# Sheet3.net
KiCad netlist of a schematic drawn in Altium Designer
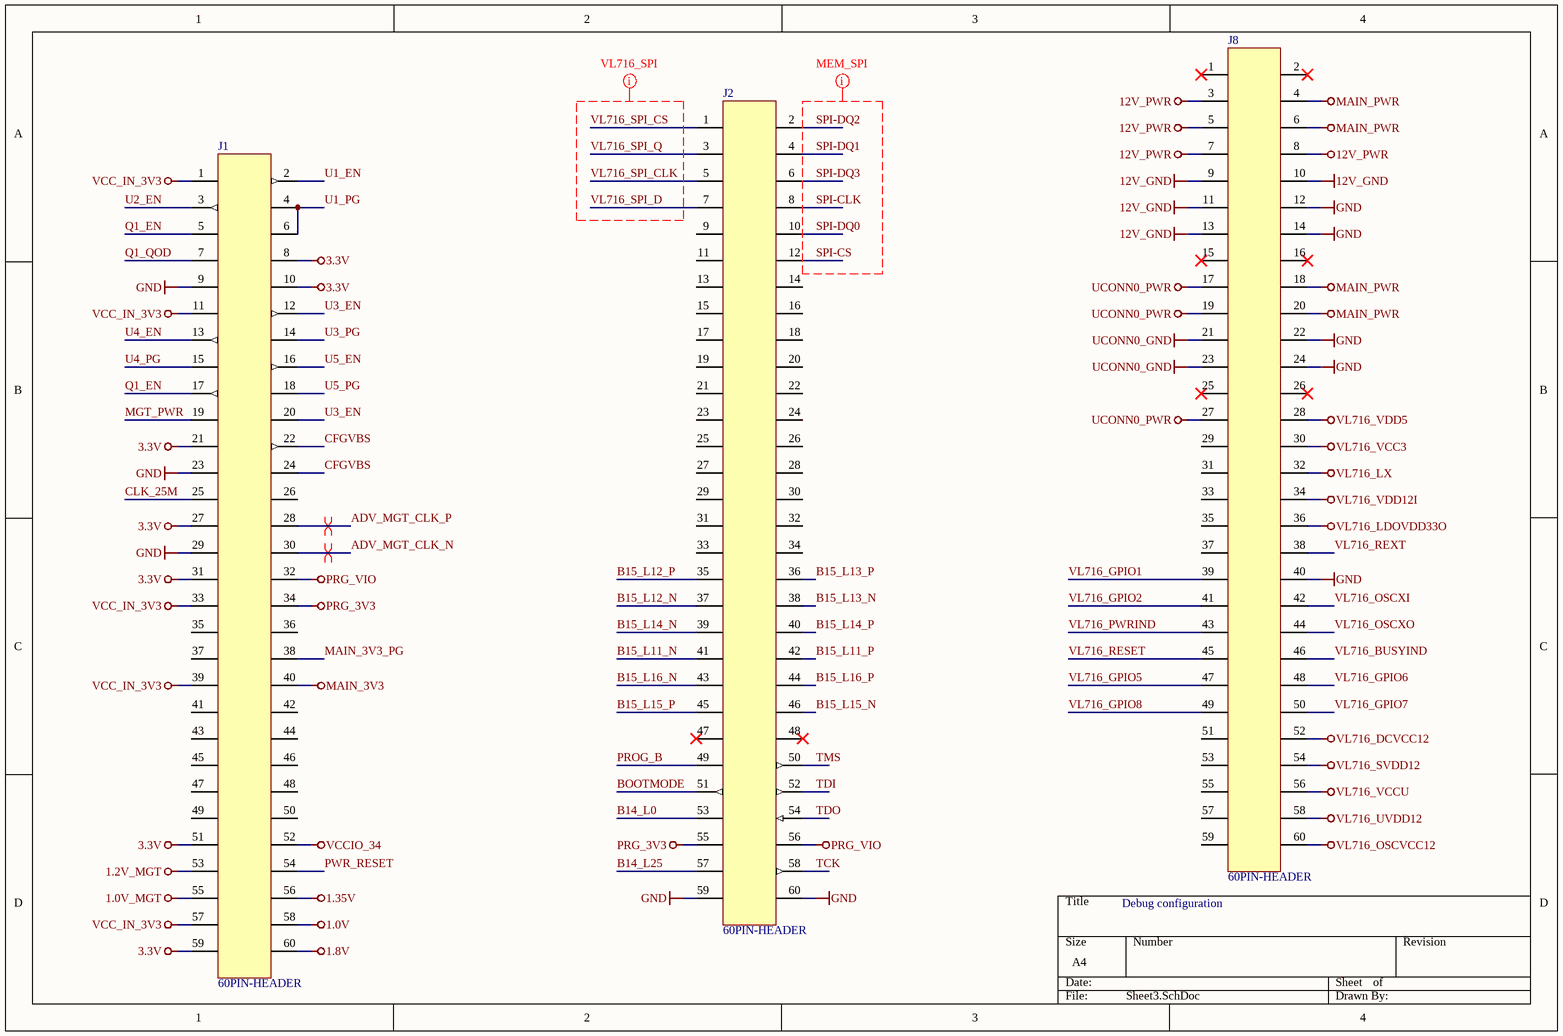
[diagram p0: Sheet3.SchDoc]

(export (version "E")
  (design (tool "Eeschema 10.0.6"))
  (components
    (comp (ref "J1")
      (value "60PIN-HEADER")
      (footprint "60PIN-HEADER")
      (description "2.54mm 60-pin header")
      (libsource (lib "Integrated_Library") (part "60PIN-HEADER"))
    )
    (comp (ref "J2")
      (value "60PIN-HEADER")
      (footprint "60PIN-HEADER")
      (description "2.54mm 60-pin header")
      (libsource (lib "Integrated_Library") (part "60PIN-HEADER"))
    )
    (comp (ref "J8")
      (value "60PIN-HEADER")
      (footprint "60PIN-HEADER")
      (description "2.54mm 60-pin header")
      (libsource (lib "Integrated_Library") (part "60PIN-HEADER"))
    )
  )
  (nets
    (net (code "1") (name "/ADV_MGT_CLK_N") (class "Default")
      (node (ref "J1") (pin "30") (pintype "passive"))
    )
    (net (code "2") (name "/ADV_MGT_CLK_P") (class "Default")
      (node (ref "J1") (pin "28") (pintype "passive"))
    )
    (net (code "3") (name "/B14_L0") (class "Default") (node (ref "J2") (pin "53") (pintype "passive")))
    (net (code "4") (name "/B14_L25") (class "Default") (node (ref "J2") (pin "57") (pintype "passive")))
    (net (code "5") (name "/B15_L11_N") (class "Default") (node (ref "J2") (pin "41") (pintype "passive")))
    (net (code "6") (name "/B15_L11_P") (class "Default") (node (ref "J2") (pin "42") (pintype "passive")))
    (net (code "7") (name "/B15_L12_N") (class "Default") (node (ref "J2") (pin "37") (pintype "passive")))
    (net (code "8") (name "/B15_L12_P") (class "Default") (node (ref "J2") (pin "35") (pintype "passive")))
    (net (code "9") (name "/B15_L13_N") (class "Default") (node (ref "J2") (pin "38") (pintype "passive")))
    (net (code "10") (name "/B15_L13_P") (class "Default") (node (ref "J2") (pin "36") (pintype "passive")))
    (net (code "11") (name "/B15_L14_N") (class "Default") (node (ref "J2") (pin "39") (pintype "passive")))
    (net (code "12") (name "/B15_L14_P") (class "Default") (node (ref "J2") (pin "40") (pintype "passive")))
    (net (code "13") (name "/B15_L15_N") (class "Default") (node (ref "J2") (pin "46") (pintype "passive")))
    (net (code "14") (name "/B15_L15_P") (class "Default") (node (ref "J2") (pin "45") (pintype "passive")))
    (net (code "15") (name "/B15_L16_N") (class "Default") (node (ref "J2") (pin "43") (pintype "passive")))
    (net (code "16") (name "/B15_L16_P") (class "Default") (node (ref "J2") (pin "44") (pintype "passive")))
    (net (code "17") (name "/BOOTMODE") (class "Default") (node (ref "J2") (pin "51") (pintype "passive")))
    (net (code "18") (name "/CFGVBS") (class "Default")
      (node (ref "J1") (pin "22") (pintype "output"))
      (node (ref "J1") (pin "24") (pintype "passive"))
    )
    (net (code "19") (name "/CLK_25M") (class "Default") (node (ref "J1") (pin "25") (pintype "passive")))
    (net (code "20") (name "/MAIN_3V3_PG") (class "Default") (node (ref "J1") (pin "38") (pintype "passive")))
    (net (code "21") (name "/MGT_PWR") (class "Default") (node (ref "J1") (pin "19") (pintype "passive")))
    (net (code "22") (name "/PROG_B") (class "Default") (node (ref "J2") (pin "49") (pintype "passive")))
    (net (code "23") (name "/PWR_RESET") (class "Default") (node (ref "J1") (pin "54") (pintype "passive")))
    (net (code "24") (name "/Q1_EN") (class "Default")
      (node (ref "J1") (pin "17") (pintype "output"))
      (node (ref "J1") (pin "5") (pintype "passive"))
    )
    (net (code "25") (name "/Q1_QOD") (class "Default") (node (ref "J1") (pin "7") (pintype "passive")))
    (net (code "26") (name "/SPI-CLK") (class "Default") (node (ref "J2") (pin "8") (pintype "power_in")))
    (net (code "27") (name "/SPI-CS") (class "Default") (node (ref "J2") (pin "12") (pintype "output")))
    (net (code "28") (name "/SPI-DQ0") (class "Default") (node (ref "J2") (pin "10") (pintype "power_in")))
    (net (code "29") (name "/SPI-DQ1") (class "Default") (node (ref "J2") (pin "4") (pintype "passive")))
    (net (code "30") (name "/SPI-DQ2") (class "Default") (node (ref "J2") (pin "2") (pintype "output")))
    (net (code "31") (name "/SPI-DQ3") (class "Default") (node (ref "J2") (pin "6") (pintype "passive")))
    (net (code "32") (name "/TCK") (class "Default") (node (ref "J2") (pin "58") (pintype "passive")))
    (net (code "33") (name "/TDI") (class "Default") (node (ref "J2") (pin "52") (pintype "passive")))
    (net (code "34") (name "/TDO") (class "Default") (node (ref "J2") (pin "54") (pintype "passive")))
    (net (code "35") (name "/TMS") (class "Default") (node (ref "J2") (pin "50") (pintype "passive")))
    (net (code "36") (name "/U1_EN") (class "Default") (node (ref "J1") (pin "2") (pintype "output")))
    (net (code "37") (name "/U1_PG") (class "Default")
      (node (ref "J1") (pin "4") (pintype "passive"))
      (node (ref "J1") (pin "6") (pintype "passive"))
    )
    (net (code "38") (name "/U2_EN") (class "Default") (node (ref "J1") (pin "3") (pintype "output")))
    (net (code "39") (name "/U3_EN") (class "Default")
      (node (ref "J1") (pin "12") (pintype "output"))
      (node (ref "J1") (pin "20") (pintype "passive"))
    )
    (net (code "40") (name "/U3_PG") (class "Default") (node (ref "J1") (pin "14") (pintype "passive")))
    (net (code "41") (name "/U4_EN") (class "Default") (node (ref "J1") (pin "13") (pintype "output")))
    (net (code "42") (name "/U4_PG") (class "Default") (node (ref "J1") (pin "15") (pintype "passive")))
    (net (code "43") (name "/U5_EN") (class "Default") (node (ref "J1") (pin "16") (pintype "output")))
    (net (code "44") (name "/U5_PG") (class "Default") (node (ref "J1") (pin "18") (pintype "passive")))
    (net (code "45") (name "/VL716_BUSYIND") (class "Default")
      (node (ref "J8") (pin "46") (pintype "passive"))
    )
    (net (code "46") (name "/VL716_GPIO1") (class "Default") (node (ref "J8") (pin "39") (pintype "passive")))
    (net (code "47") (name "/VL716_GPIO2") (class "Default") (node (ref "J8") (pin "41") (pintype "passive")))
    (net (code "48") (name "/VL716_GPIO5") (class "Default") (node (ref "J8") (pin "47") (pintype "passive")))
    (net (code "49") (name "/VL716_GPIO6") (class "Default") (node (ref "J8") (pin "48") (pintype "passive")))
    (net (code "50") (name "/VL716_GPIO7") (class "Default") (node (ref "J8") (pin "50") (pintype "passive")))
    (net (code "51") (name "/VL716_GPIO8") (class "Default") (node (ref "J8") (pin "49") (pintype "passive")))
    (net (code "52") (name "/VL716_OSCXI") (class "Default") (node (ref "J8") (pin "42") (pintype "passive")))
    (net (code "53") (name "/VL716_OSCXO") (class "Default") (node (ref "J8") (pin "44") (pintype "passive")))
    (net (code "54") (name "/VL716_PWRIND") (class "Default")
      (node (ref "J8") (pin "43") (pintype "passive"))
    )
    (net (code "55") (name "/VL716_RESET") (class "Default") (node (ref "J8") (pin "45") (pintype "passive")))
    (net (code "56") (name "/VL716_REXT") (class "Default") (node (ref "J8") (pin "38") (pintype "passive")))
    (net (code "57") (name "/VL716_SPI_CLK") (class "Default")
      (node (ref "J2") (pin "5") (pintype "passive"))
    )
    (net (code "58") (name "/VL716_SPI_CS") (class "Default") (node (ref "J2") (pin "1") (pintype "passive")))
    (net (code "59") (name "/VL716_SPI_D") (class "Default") (node (ref "J2") (pin "7") (pintype "passive")))
    (net (code "60") (name "/VL716_SPI_Q") (class "Default") (node (ref "J2") (pin "3") (pintype "output")))
    (net (code "61") (name "1.0V") (class "Default") (node (ref "J1") (pin "58") (pintype "passive")))
    (net (code "62") (name "1.0V_MGT") (class "Default") (node (ref "J1") (pin "55") (pintype "passive")))
    (net (code "63") (name "1.2V_MGT") (class "Default") (node (ref "J1") (pin "53") (pintype "passive")))
    (net (code "64") (name "1.8V") (class "Default") (node (ref "J1") (pin "60") (pintype "passive")))
    (net (code "65") (name "1.35V") (class "Default") (node (ref "J1") (pin "56") (pintype "passive")))
    (net (code "66") (name "3.3V") (class "Default")
      (node (ref "J1") (pin "10") (pintype "power_in"))
      (node (ref "J1") (pin "21") (pintype "passive"))
      (node (ref "J1") (pin "27") (pintype "passive"))
      (node (ref "J1") (pin "31") (pintype "passive"))
      (node (ref "J1") (pin "51") (pintype "passive"))
      (node (ref "J1") (pin "59") (pintype "passive"))
      (node (ref "J1") (pin "8") (pintype "power_in"))
    )
    (net (code "67") (name "12V_GND") (class "Default")
      (node (ref "J8") (pin "10") (pintype "power_in"))
      (node (ref "J8") (pin "11") (pintype "passive"))
      (node (ref "J8") (pin "13") (pintype "output"))
      (node (ref "J8") (pin "9") (pintype "passive"))
    )
    (net (code "68") (name "12V_PWR") (class "Default")
      (node (ref "J8") (pin "3") (pintype "output"))
      (node (ref "J8") (pin "5") (pintype "passive"))
      (node (ref "J8") (pin "7") (pintype "passive"))
      (node (ref "J8") (pin "8") (pintype "power_in"))
    )
    (net (code "69") (name "GND") (class "Default")
      (node (ref "J1") (pin "23") (pintype "passive"))
      (node (ref "J1") (pin "29") (pintype "passive"))
      (node (ref "J1") (pin "9") (pintype "passive"))
      (node (ref "J2") (pin "59") (pintype "passive"))
      (node (ref "J2") (pin "60") (pintype "passive"))
      (node (ref "J8") (pin "12") (pintype "output"))
      (node (ref "J8") (pin "14") (pintype "passive"))
      (node (ref "J8") (pin "22") (pintype "output"))
      (node (ref "J8") (pin "24") (pintype "passive"))
      (node (ref "J8") (pin "40") (pintype "passive"))
    )
    (net (code "70") (name "MAIN_3V3") (class "Default") (node (ref "J1") (pin "40") (pintype "passive")))
    (net (code "71") (name "MAIN_PWR") (class "Default")
      (node (ref "J8") (pin "18") (pintype "passive"))
      (node (ref "J8") (pin "20") (pintype "passive"))
      (node (ref "J8") (pin "4") (pintype "passive"))
      (node (ref "J8") (pin "6") (pintype "passive"))
    )
    (net (code "72") (name "PRG_3V3") (class "Default")
      (node (ref "J1") (pin "34") (pintype "passive"))
      (node (ref "J2") (pin "55") (pintype "passive"))
    )
    (net (code "73") (name "PRG_VIO") (class "Default")
      (node (ref "J1") (pin "32") (pintype "passive"))
      (node (ref "J2") (pin "56") (pintype "passive"))
    )
    (net (code "74") (name "UCONN0_GND") (class "Default")
      (node (ref "J8") (pin "21") (pintype "passive"))
      (node (ref "J8") (pin "23") (pintype "passive"))
    )
    (net (code "75") (name "UCONN0_PWR") (class "Default")
      (node (ref "J8") (pin "17") (pintype "output"))
      (node (ref "J8") (pin "19") (pintype "passive"))
      (node (ref "J8") (pin "27") (pintype "passive"))
    )
    (net (code "76") (name "VCCIO_34") (class "Default") (node (ref "J1") (pin "52") (pintype "passive")))
    (net (code "77") (name "VCC_IN_3V3") (class "Default")
      (node (ref "J1") (pin "1") (pintype "passive"))
      (node (ref "J1") (pin "11") (pintype "passive"))
      (node (ref "J1") (pin "33") (pintype "passive"))
      (node (ref "J1") (pin "39") (pintype "passive"))
      (node (ref "J1") (pin "57") (pintype "passive"))
    )
    (net (code "78") (name "VL716_DCVCC12") (class "Default")
      (node (ref "J8") (pin "52") (pintype "passive"))
    )
    (net (code "79") (name "VL716_LDOVDD33O") (class "Default")
      (node (ref "J8") (pin "36") (pintype "passive"))
    )
    (net (code "80") (name "VL716_LX") (class "Default") (node (ref "J8") (pin "32") (pintype "passive")))
    (net (code "81") (name "VL716_OSCVCC12") (class "Default")
      (node (ref "J8") (pin "60") (pintype "passive"))
    )
    (net (code "82") (name "VL716_SVDD12") (class "Default") (node (ref "J8") (pin "54") (pintype "passive")))
    (net (code "83") (name "VL716_UVDD12") (class "Default") (node (ref "J8") (pin "58") (pintype "passive")))
    (net (code "84") (name "VL716_VCC3") (class "Default") (node (ref "J8") (pin "30") (pintype "passive")))
    (net (code "85") (name "VL716_VCCU") (class "Default") (node (ref "J8") (pin "56") (pintype "passive")))
    (net (code "86") (name "VL716_VDD5") (class "Default") (node (ref "J8") (pin "28") (pintype "passive")))
    (net (code "87") (name "VL716_VDD12I") (class "Default") (node (ref "J8") (pin "34") (pintype "passive")))
    (net (code "88") (name "unconnected-(J1-Pad26)") (class "Default")
      (node (ref "J1") (pin "26") (pintype "passive"))
    )
    (net (code "89") (name "unconnected-(J1-Pad35)") (class "Default")
      (node (ref "J1") (pin "35") (pintype "passive"))
    )
    (net (code "90") (name "unconnected-(J1-Pad36)") (class "Default")
      (node (ref "J1") (pin "36") (pintype "passive"))
    )
    (net (code "91") (name "unconnected-(J1-Pad37)") (class "Default")
      (node (ref "J1") (pin "37") (pintype "passive"))
    )
    (net (code "92") (name "unconnected-(J1-Pad41)") (class "Default")
      (node (ref "J1") (pin "41") (pintype "passive"))
    )
    (net (code "93") (name "unconnected-(J1-Pad42)") (class "Default")
      (node (ref "J1") (pin "42") (pintype "passive"))
    )
    (net (code "94") (name "unconnected-(J1-Pad43)") (class "Default")
      (node (ref "J1") (pin "43") (pintype "passive"))
    )
    (net (code "95") (name "unconnected-(J1-Pad44)") (class "Default")
      (node (ref "J1") (pin "44") (pintype "passive"))
    )
    (net (code "96") (name "unconnected-(J1-Pad45)") (class "Default")
      (node (ref "J1") (pin "45") (pintype "passive"))
    )
    (net (code "97") (name "unconnected-(J1-Pad46)") (class "Default")
      (node (ref "J1") (pin "46") (pintype "passive"))
    )
    (net (code "98") (name "unconnected-(J1-Pad47)") (class "Default")
      (node (ref "J1") (pin "47") (pintype "passive"))
    )
    (net (code "99") (name "unconnected-(J1-Pad48)") (class "Default")
      (node (ref "J1") (pin "48") (pintype "passive"))
    )
    (net (code "100") (name "unconnected-(J1-Pad49)") (class "Default")
      (node (ref "J1") (pin "49") (pintype "passive"))
    )
    (net (code "101") (name "unconnected-(J1-Pad50)") (class "Default")
      (node (ref "J1") (pin "50") (pintype "passive"))
    )
    (net (code "102") (name "unconnected-(J2-Pad9)") (class "Default")
      (node (ref "J2") (pin "9") (pintype "passive"))
    )
    (net (code "103") (name "unconnected-(J2-Pad11)") (class "Default")
      (node (ref "J2") (pin "11") (pintype "passive"))
    )
    (net (code "104") (name "unconnected-(J2-Pad13)") (class "Default")
      (node (ref "J2") (pin "13") (pintype "output"))
    )
    (net (code "105") (name "unconnected-(J2-Pad14)") (class "Default")
      (node (ref "J2") (pin "14") (pintype "passive"))
    )
    (net (code "106") (name "unconnected-(J2-Pad15)") (class "Default")
      (node (ref "J2") (pin "15") (pintype "passive"))
    )
    (net (code "107") (name "unconnected-(J2-Pad16)") (class "Default")
      (node (ref "J2") (pin "16") (pintype "output"))
    )
    (net (code "108") (name "unconnected-(J2-Pad17)") (class "Default")
      (node (ref "J2") (pin "17") (pintype "output"))
    )
    (net (code "109") (name "unconnected-(J2-Pad18)") (class "Default")
      (node (ref "J2") (pin "18") (pintype "passive"))
    )
    (net (code "110") (name "unconnected-(J2-Pad19)") (class "Default")
      (node (ref "J2") (pin "19") (pintype "passive"))
    )
    (net (code "111") (name "unconnected-(J2-Pad20)") (class "Default")
      (node (ref "J2") (pin "20") (pintype "passive"))
    )
    (net (code "112") (name "unconnected-(J2-Pad21)") (class "Default")
      (node (ref "J2") (pin "21") (pintype "passive"))
    )
    (net (code "113") (name "unconnected-(J2-Pad22)") (class "Default")
      (node (ref "J2") (pin "22") (pintype "output"))
    )
    (net (code "114") (name "unconnected-(J2-Pad23)") (class "Default")
      (node (ref "J2") (pin "23") (pintype "passive"))
    )
    (net (code "115") (name "unconnected-(J2-Pad24)") (class "Default")
      (node (ref "J2") (pin "24") (pintype "passive"))
    )
    (net (code "116") (name "unconnected-(J2-Pad25)") (class "Default")
      (node (ref "J2") (pin "25") (pintype "passive"))
    )
    (net (code "117") (name "unconnected-(J2-Pad26)") (class "Default")
      (node (ref "J2") (pin "26") (pintype "passive"))
    )
    (net (code "118") (name "unconnected-(J2-Pad27)") (class "Default")
      (node (ref "J2") (pin "27") (pintype "passive"))
    )
    (net (code "119") (name "unconnected-(J2-Pad28)") (class "Default")
      (node (ref "J2") (pin "28") (pintype "passive"))
    )
    (net (code "120") (name "unconnected-(J2-Pad29)") (class "Default")
      (node (ref "J2") (pin "29") (pintype "passive"))
    )
    (net (code "121") (name "unconnected-(J2-Pad30)") (class "Default")
      (node (ref "J2") (pin "30") (pintype "passive"))
    )
    (net (code "122") (name "unconnected-(J2-Pad31)") (class "Default")
      (node (ref "J2") (pin "31") (pintype "passive"))
    )
    (net (code "123") (name "unconnected-(J2-Pad32)") (class "Default")
      (node (ref "J2") (pin "32") (pintype "passive"))
    )
    (net (code "124") (name "unconnected-(J2-Pad33)") (class "Default")
      (node (ref "J2") (pin "33") (pintype "passive"))
    )
    (net (code "125") (name "unconnected-(J2-Pad34)") (class "Default")
      (node (ref "J2") (pin "34") (pintype "passive"))
    )
    (net (code "126") (name "unconnected-(J2-Pad47)") (class "Default")
      (node (ref "J2") (pin "47") (pintype "passive+no_connect"))
    )
    (net (code "127") (name "unconnected-(J2-Pad48)") (class "Default")
      (node (ref "J2") (pin "48") (pintype "passive+no_connect"))
    )
    (net (code "128") (name "unconnected-(J8-Pad1)") (class "Default")
      (node (ref "J8") (pin "1") (pintype "passive+no_connect"))
    )
    (net (code "129") (name "unconnected-(J8-Pad2)") (class "Default")
      (node (ref "J8") (pin "2") (pintype "output+no_connect"))
    )
    (net (code "130") (name "unconnected-(J8-Pad15)") (class "Default")
      (node (ref "J8") (pin "15") (pintype "passive+no_connect"))
    )
    (net (code "131") (name "unconnected-(J8-Pad16)") (class "Default")
      (node (ref "J8") (pin "16") (pintype "output+no_connect"))
    )
    (net (code "132") (name "unconnected-(J8-Pad25)") (class "Default")
      (node (ref "J8") (pin "25") (pintype "passive+no_connect"))
    )
    (net (code "133") (name "unconnected-(J8-Pad26)") (class "Default")
      (node (ref "J8") (pin "26") (pintype "passive+no_connect"))
    )
    (net (code "134") (name "unconnected-(J8-Pad29)") (class "Default")
      (node (ref "J8") (pin "29") (pintype "passive"))
    )
    (net (code "135") (name "unconnected-(J8-Pad31)") (class "Default")
      (node (ref "J8") (pin "31") (pintype "passive"))
    )
    (net (code "136") (name "unconnected-(J8-Pad33)") (class "Default")
      (node (ref "J8") (pin "33") (pintype "passive"))
    )
    (net (code "137") (name "unconnected-(J8-Pad35)") (class "Default")
      (node (ref "J8") (pin "35") (pintype "passive"))
    )
    (net (code "138") (name "unconnected-(J8-Pad37)") (class "Default")
      (node (ref "J8") (pin "37") (pintype "passive"))
    )
    (net (code "139") (name "unconnected-(J8-Pad51)") (class "Default")
      (node (ref "J8") (pin "51") (pintype "passive"))
    )
    (net (code "140") (name "unconnected-(J8-Pad53)") (class "Default")
      (node (ref "J8") (pin "53") (pintype "passive"))
    )
    (net (code "141") (name "unconnected-(J8-Pad55)") (class "Default")
      (node (ref "J8") (pin "55") (pintype "passive"))
    )
    (net (code "142") (name "unconnected-(J8-Pad57)") (class "Default")
      (node (ref "J8") (pin "57") (pintype "passive"))
    )
    (net (code "143") (name "unconnected-(J8-Pad59)") (class "Default")
      (node (ref "J8") (pin "59") (pintype "passive"))
    )
  )
)
